# mini-v1_9.net
KiCad netlist of a schematic drawn in EAGLE
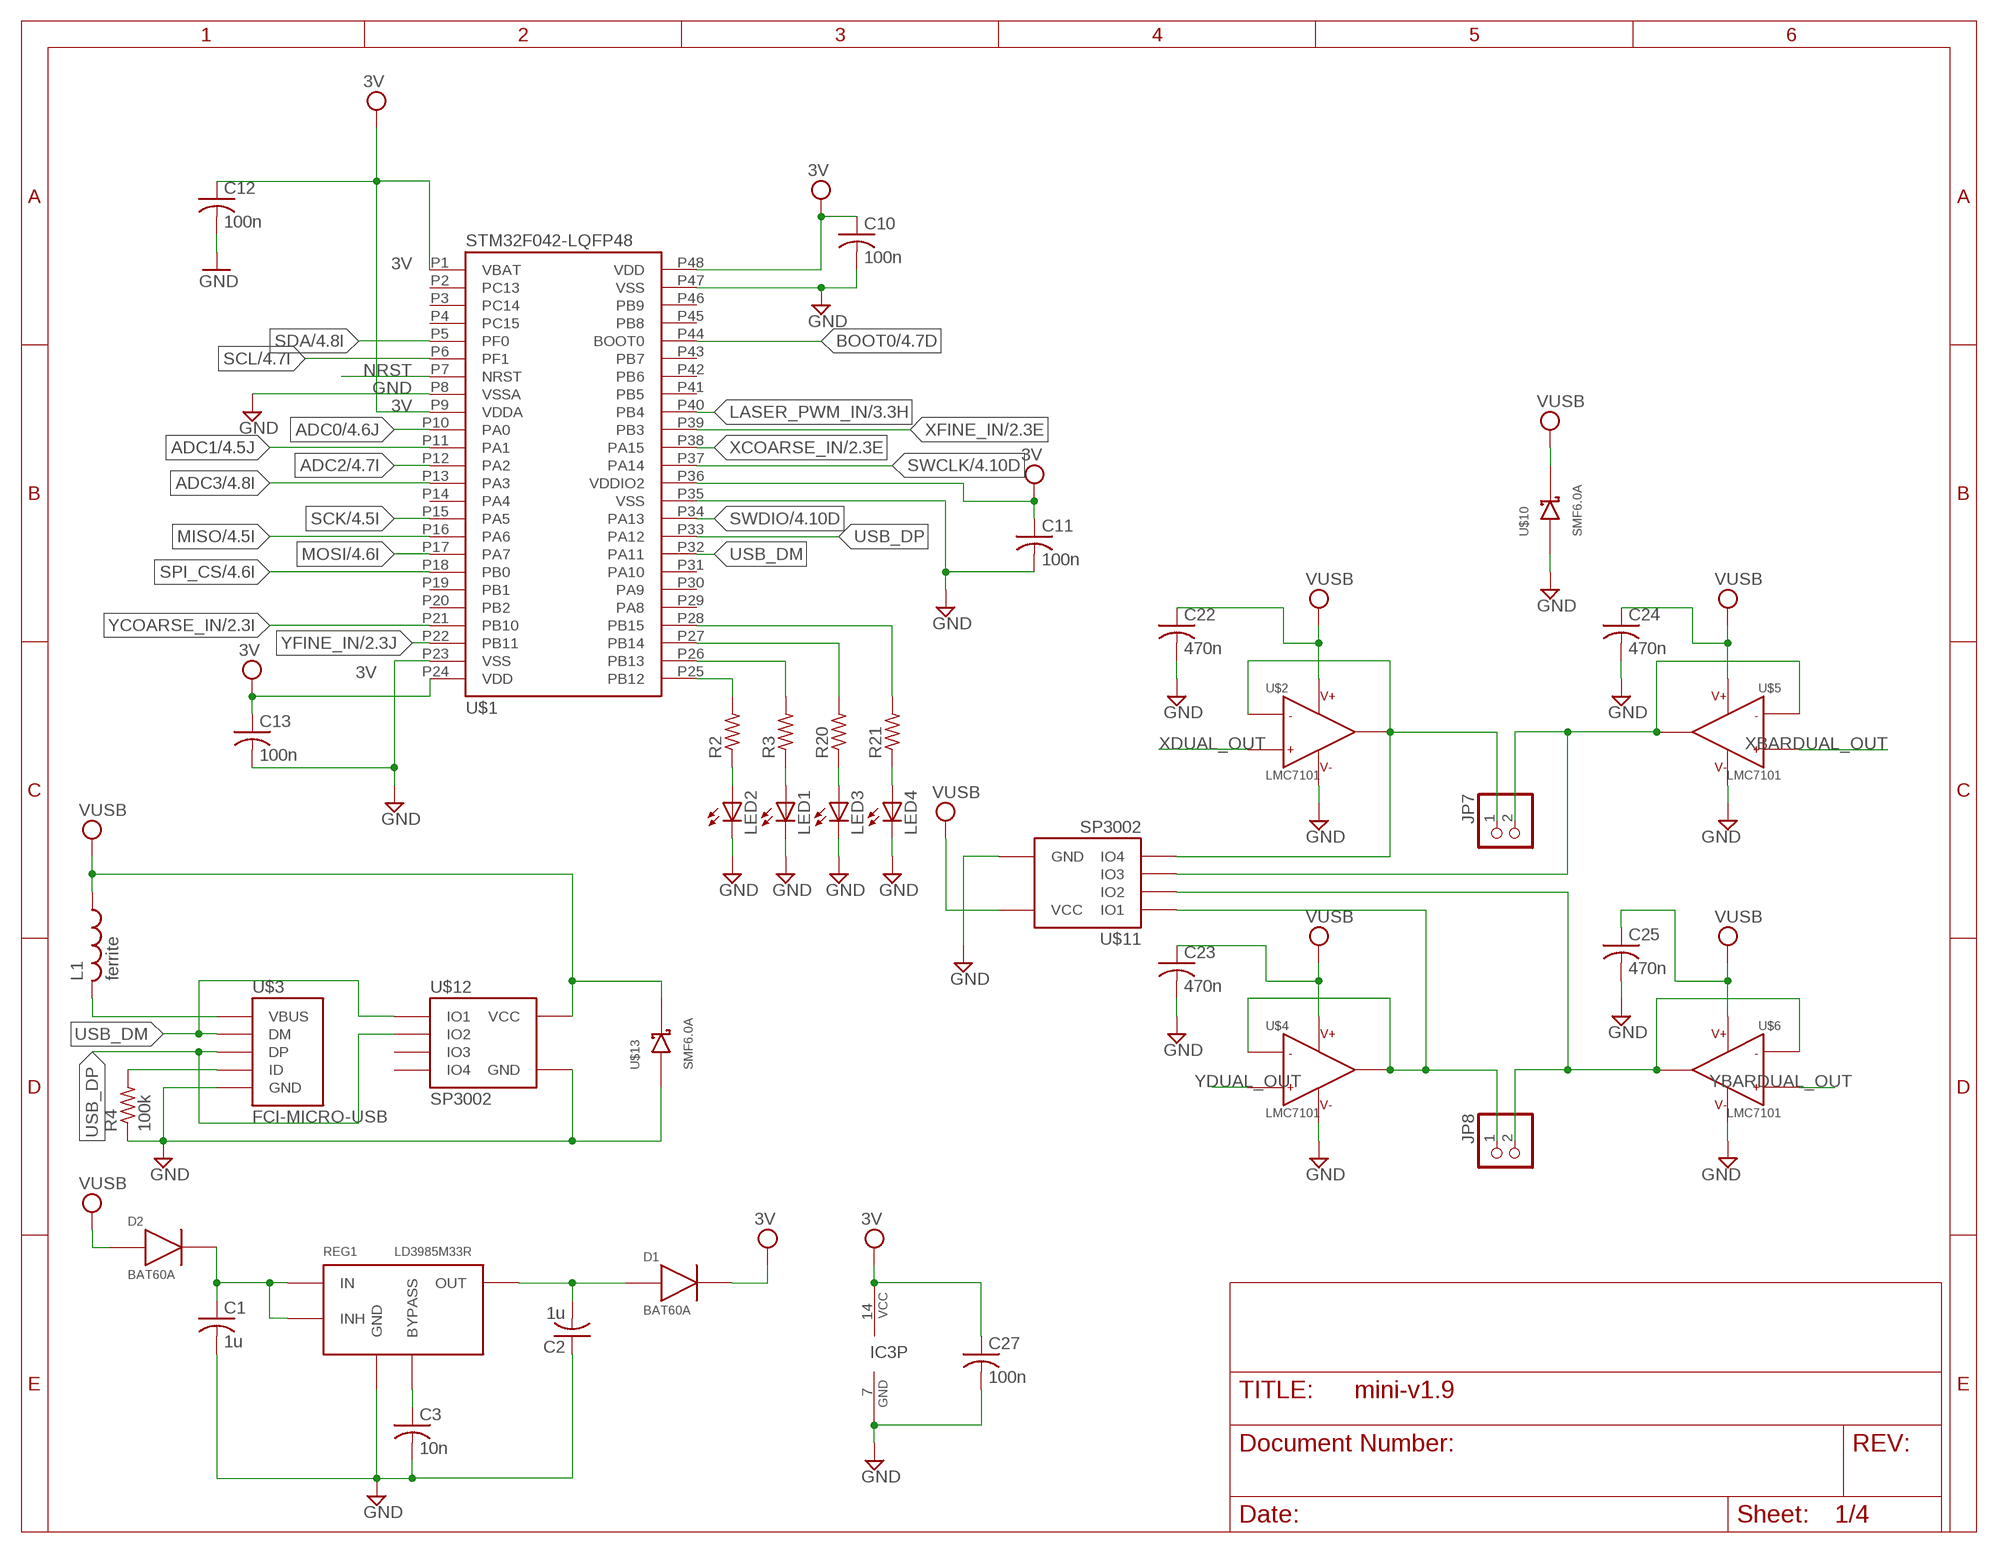
[diagram p0: schematic, sheet 1]
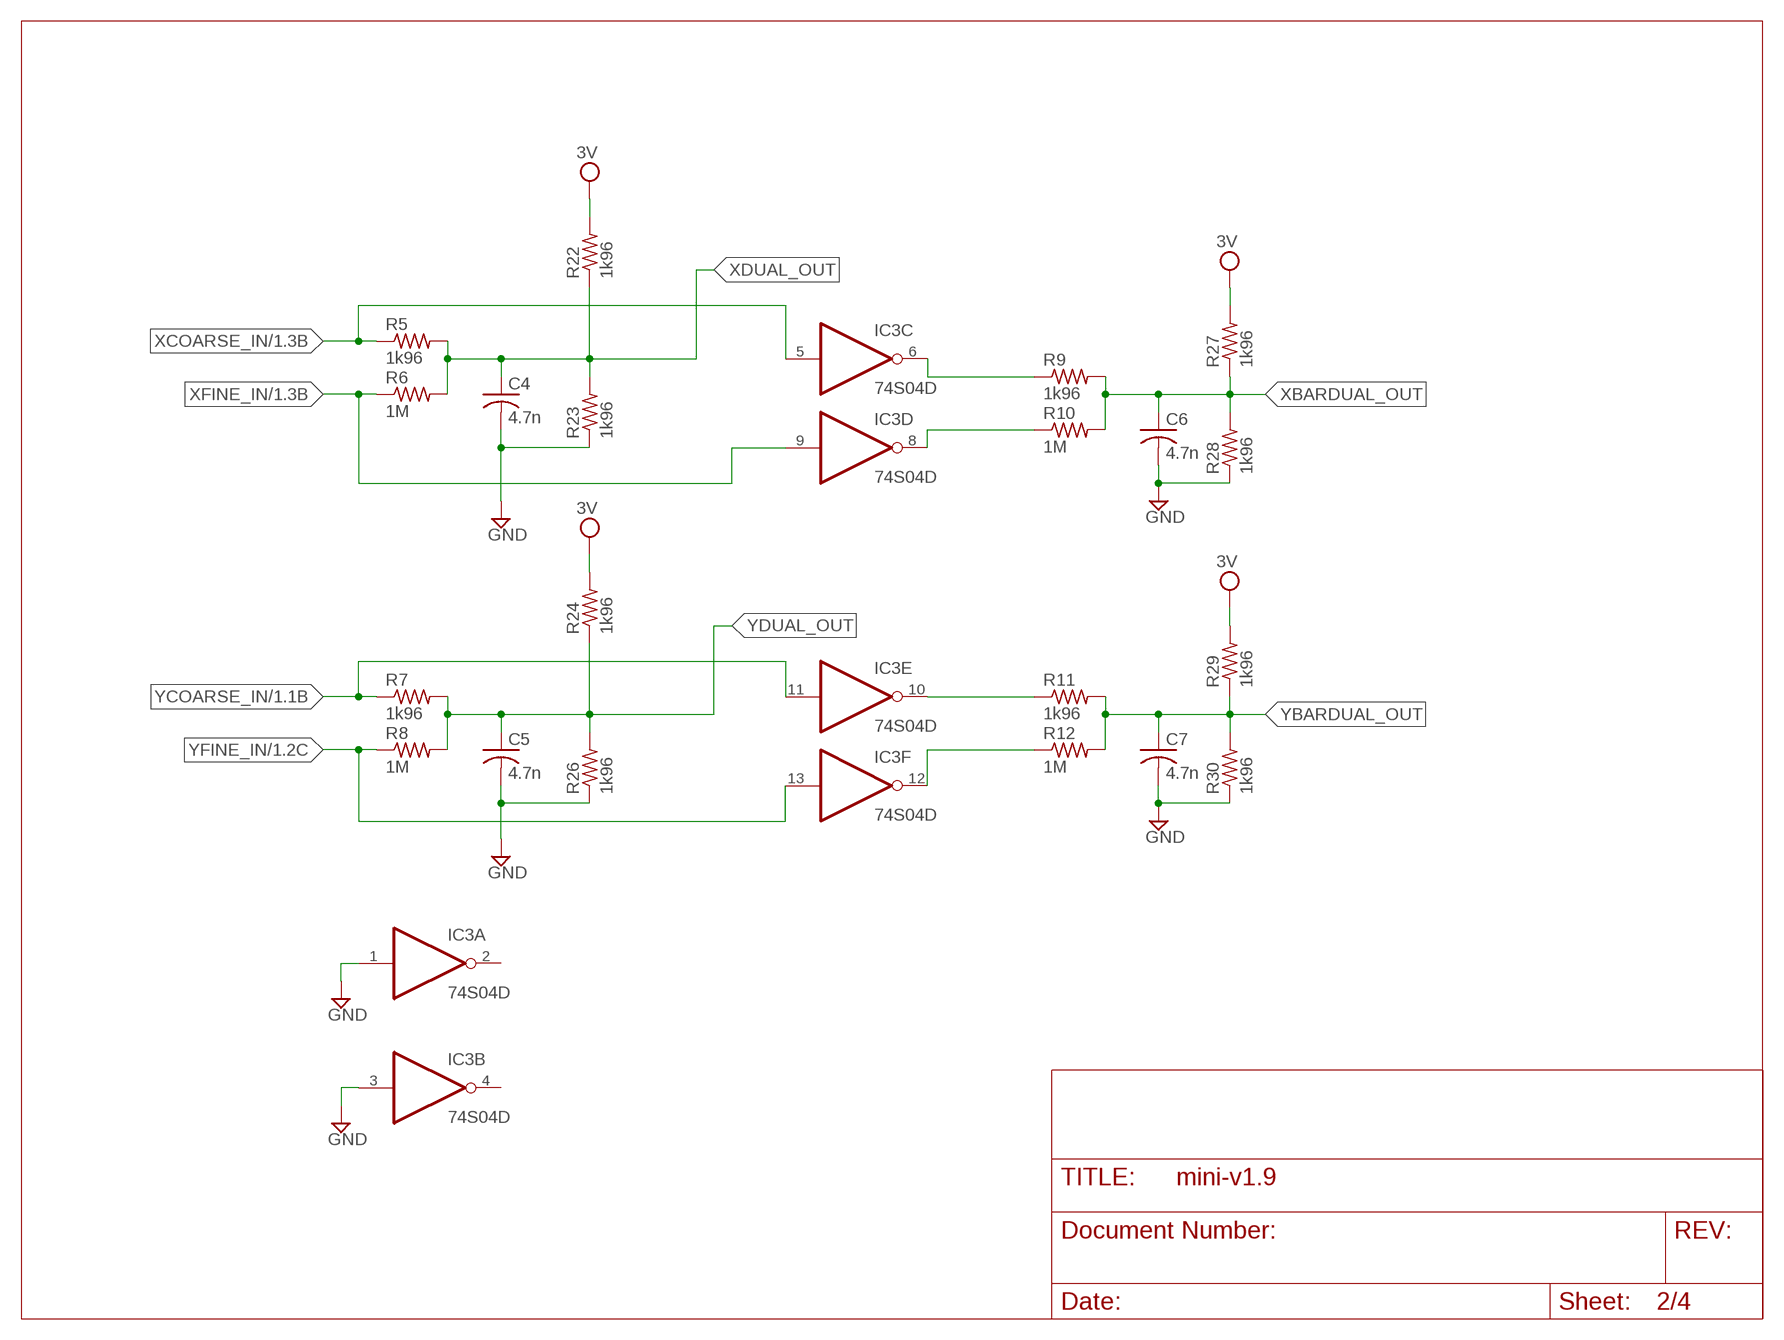
[diagram p1: schematic, sheet 2]
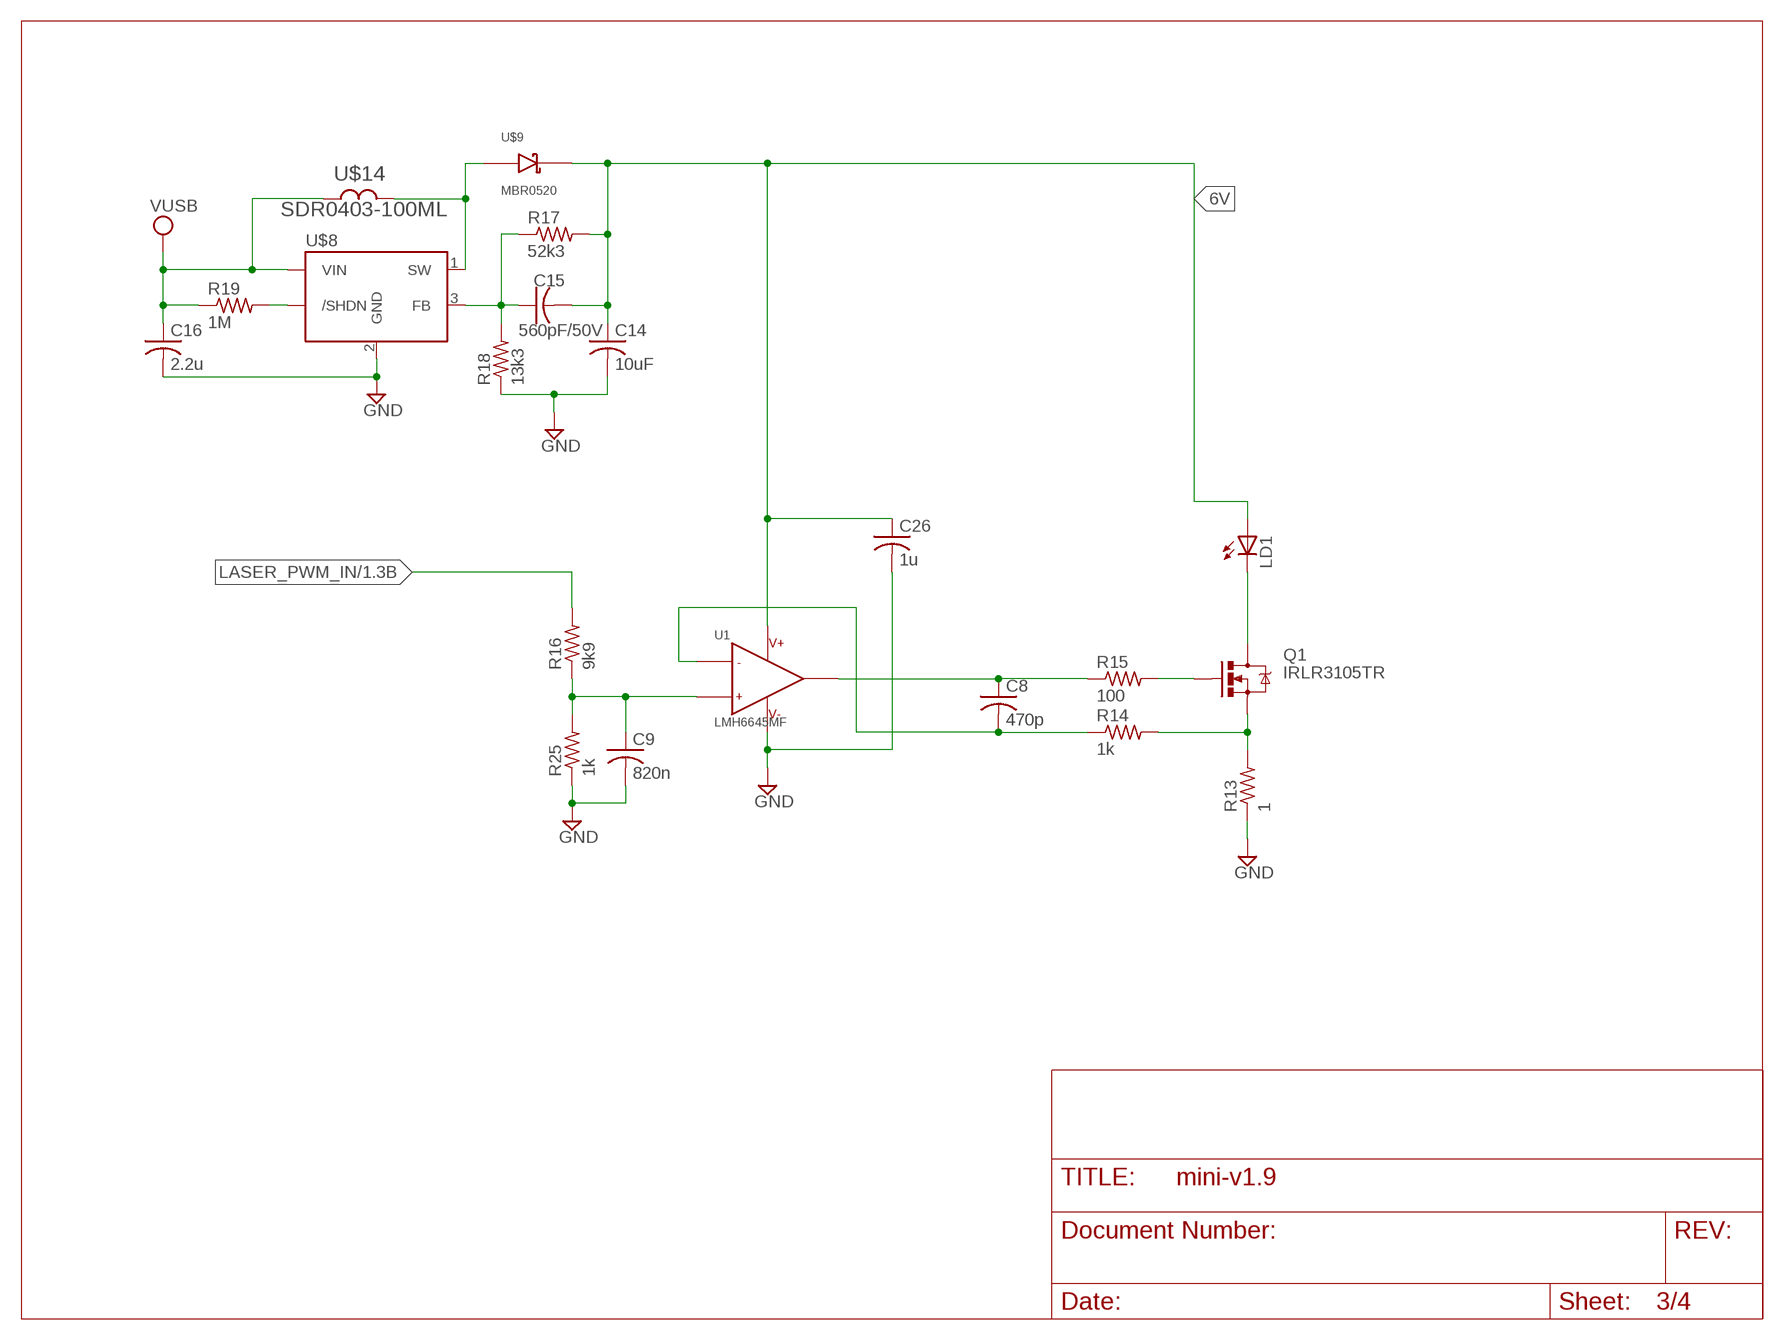
[diagram p2: schematic, sheet 3]
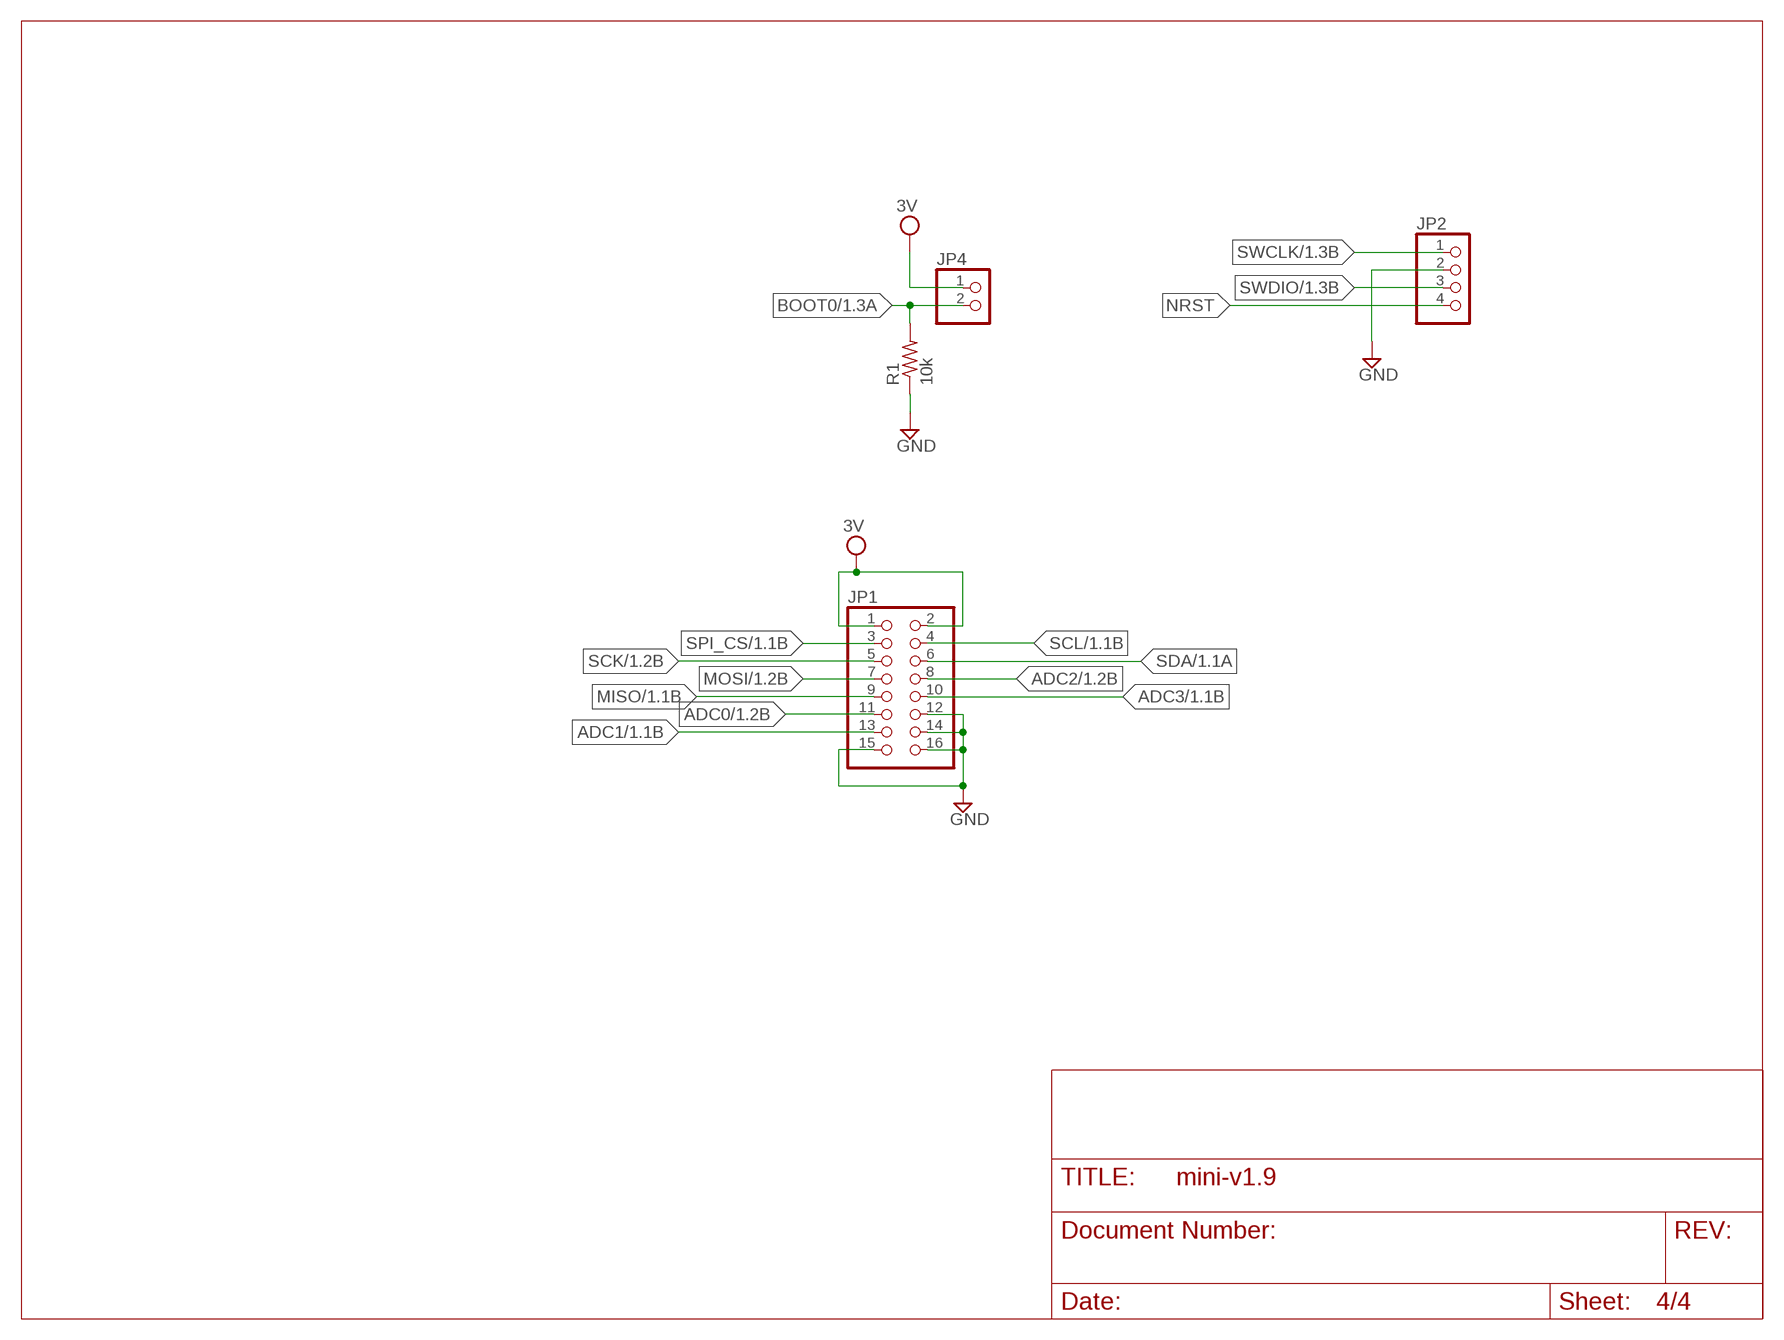
[diagram p3: schematic, sheet 4]

(export (version "E")
  (design (tool "Eeschema 10.0.6"))
  (components
    (comp (ref "JP1")
      (value "PINHD-2X8")
      (footprint "eagle-import:2X08")
      (libsource (lib "eagle-import") (part "PINHD-2X8"))
    )
    (comp (ref "JP2")
      (value "PINHD-1X4")
      (footprint "eagle-import:1X04")
      (libsource (lib "eagle-import") (part "PINHD-1X4"))
    )
    (comp (ref "JP4")
      (value "PINHD-1X2")
      (footprint "eagle-import:1X02")
      (libsource (lib "eagle-import") (part "PINHD-1X2"))
    )
    (comp (ref "R1")
      (value "10k")
      (footprint "eagle-import:R0603")
      (libsource (lib "eagle-import") (part "R-US_R0603"))
    )
    (comp (ref "C8")
      (value "470p")
      (footprint "eagle-import:C0603")
      (libsource (lib "eagle-import") (part "C-USC0603"))
    )
    (comp (ref "C9")
      (value "820n")
      (footprint "eagle-import:C0603")
      (libsource (lib "eagle-import") (part "C-USC0603"))
    )
    (comp (ref "C14")
      (value "10uF")
      (footprint "eagle-import:C0603")
      (libsource (lib "eagle-import") (part "C-USC0603"))
    )
    (comp (ref "C15")
      (value "560pF/50V")
      (footprint "eagle-import:C0603")
      (libsource (lib "eagle-import") (part "C-USC0603"))
    )
    (comp (ref "C16")
      (value "2.2u")
      (footprint "eagle-import:C0603")
      (libsource (lib "eagle-import") (part "C-USC0603"))
    )
    (comp (ref "C26")
      (value "1u")
      (footprint "eagle-import:C0603")
      (libsource (lib "eagle-import") (part "C-USC0603"))
    )
    (comp (ref "LD1")
      (value "LASERDIODELD2")
      (footprint "eagle-import:LASERDIODE2")
      (fields (field (name "MPN") "3 x (0552-2-15-15-11-27-10-0)"))
      (libsource (lib "eagle-import") (part "LASERDIODELD2"))
    )
    (comp (ref "Q1")
      (value "IRLR3105TR")
      (footprint "eagle-import:DPAK")
      (libsource (lib "eagle-import") (part "FET-N-IRLR3105TRIRLR3105TR"))
    )
    (comp (ref "R13")
      (value "1")
      (footprint "eagle-import:R0603")
      (libsource (lib "eagle-import") (part "R-US_R0603"))
    )
    (comp (ref "R14")
      (value "1k")
      (footprint "eagle-import:R0603")
      (libsource (lib "eagle-import") (part "R-US_R0603"))
    )
    (comp (ref "R15")
      (value "100")
      (footprint "eagle-import:R0603")
      (libsource (lib "eagle-import") (part "R-US_R0603"))
    )
    (comp (ref "R16")
      (value "9k9")
      (footprint "eagle-import:R0603")
      (libsource (lib "eagle-import") (part "R-US_R0603"))
    )
    (comp (ref "R17")
      (value "52k3")
      (footprint "eagle-import:R0603")
      (libsource (lib "eagle-import") (part "R-US_R0603"))
    )
    (comp (ref "R18")
      (value "13k3")
      (footprint "eagle-import:R0603")
      (libsource (lib "eagle-import") (part "R-US_R0603"))
    )
    (comp (ref "R19")
      (value "1M")
      (footprint "eagle-import:R0603")
      (libsource (lib "eagle-import") (part "R-US_R0603"))
    )
    (comp (ref "R25")
      (value "1k")
      (footprint "eagle-import:R0603")
      (libsource (lib "eagle-import") (part "R-US_R0603"))
    )
    (comp (ref "U$8")
      (value "LMR62014")
      (footprint "eagle-import:SOT23-5")
      (libsource (lib "eagle-import") (part "LMR62014"))
    )
    (comp (ref "U$9")
      (value "MBR0520")
      (footprint "eagle-import:SOD123")
      (libsource (lib "eagle-import") (part "MBR0520"))
    )
    (comp (ref "U$14")
      (value "SDR0403-100ML")
      (footprint "eagle-import:SDR0403")
      (libsource (lib "eagle-import") (part "SDR0403"))
    )
    (comp (ref "U1")
      (value "LMH6645MF")
      (footprint "eagle-import:SOT23-5")
      (libsource (lib "eagle-import") (part "OPAMP-SINGLELMH6645MF"))
    )
    (comp (ref "C1")
      (value "1u")
      (footprint "eagle-import:C0603")
      (libsource (lib "eagle-import") (part "C-USC0603"))
    )
    (comp (ref "C2")
      (value "1u")
      (footprint "eagle-import:C0603")
      (libsource (lib "eagle-import") (part "C-USC0603"))
    )
    (comp (ref "C3")
      (value "10n")
      (footprint "eagle-import:C0603")
      (libsource (lib "eagle-import") (part "C-USC0603"))
    )
    (comp (ref "C10")
      (value "100n")
      (footprint "eagle-import:C0603")
      (libsource (lib "eagle-import") (part "C-USC0603"))
    )
    (comp (ref "C11")
      (value "100n")
      (footprint "eagle-import:C0603")
      (libsource (lib "eagle-import") (part "C-USC0603"))
    )
    (comp (ref "C12")
      (value "100n")
      (footprint "eagle-import:C0603")
      (libsource (lib "eagle-import") (part "C-USC0603"))
    )
    (comp (ref "C13")
      (value "100n")
      (footprint "eagle-import:C0603")
      (libsource (lib "eagle-import") (part "C-USC0603"))
    )
    (comp (ref "C22")
      (value "470n")
      (footprint "eagle-import:C0603")
      (libsource (lib "eagle-import") (part "C-USC0603"))
    )
    (comp (ref "C23")
      (value "470n")
      (footprint "eagle-import:C0603")
      (libsource (lib "eagle-import") (part "C-USC0603"))
    )
    (comp (ref "C24")
      (value "470n")
      (footprint "eagle-import:C0603")
      (libsource (lib "eagle-import") (part "C-USC0603"))
    )
    (comp (ref "C25")
      (value "470n")
      (footprint "eagle-import:C0603")
      (libsource (lib "eagle-import") (part "C-USC0603"))
    )
    (comp (ref "C27")
      (value "100n")
      (footprint "eagle-import:C0603")
      (libsource (lib "eagle-import") (part "C-USC0603"))
    )
    (comp (ref "D1")
      (value "BAT60A")
      (footprint "eagle-import:SOD323")
      (libsource (lib "eagle-import") (part "BAT60A"))
    )
    (comp (ref "D2")
      (value "BAT60A")
      (footprint "eagle-import:SOD323")
      (libsource (lib "eagle-import") (part "BAT60A"))
    )
    (comp (ref "IC3")
      (value "74S04D")
      (footprint "eagle-import:SO14")
      (libsource (lib "eagle-import") (part "7404DS"))
    )
    (comp (ref "JP7")
      (value "PINHD-1X2")
      (footprint "eagle-import:1X02")
      (libsource (lib "eagle-import") (part "PINHD-1X2"))
    )
    (comp (ref "JP8")
      (value "PINHD-1X2")
      (footprint "eagle-import:1X02")
      (libsource (lib "eagle-import") (part "PINHD-1X2"))
    )
    (comp (ref "L1")
      (value "ferrite")
      (footprint "eagle-import:C0603")
      (libsource (lib "eagle-import") (part "L-US"))
    )
    (comp (ref "LED1")
      (value "LEDCHIP-LED0603")
      (footprint "eagle-import:CHIP-LED0603")
      (libsource (lib "eagle-import") (part "LEDCHIP-LED0603"))
    )
    (comp (ref "LED2")
      (value "LEDCHIP-LED0603")
      (footprint "eagle-import:CHIP-LED0603")
      (libsource (lib "eagle-import") (part "LEDCHIP-LED0603"))
    )
    (comp (ref "LED3")
      (value "LEDCHIP-LED0603")
      (footprint "eagle-import:CHIP-LED0603")
      (libsource (lib "eagle-import") (part "LEDCHIP-LED0603"))
    )
    (comp (ref "LED4")
      (value "LEDCHIP-LED0603")
      (footprint "eagle-import:CHIP-LED0603")
      (libsource (lib "eagle-import") (part "LEDCHIP-LED0603"))
    )
    (comp (ref "R2")
      (value "R-US_R0603")
      (footprint "eagle-import:R0603")
      (libsource (lib "eagle-import") (part "R-US_R0603"))
    )
    (comp (ref "R3")
      (value "R-US_R0603")
      (footprint "eagle-import:R0603")
      (libsource (lib "eagle-import") (part "R-US_R0603"))
    )
    (comp (ref "R4")
      (value "100k")
      (footprint "eagle-import:R0603")
      (libsource (lib "eagle-import") (part "R-US_R0603"))
    )
    (comp (ref "R20")
      (value "R-US_R0603")
      (footprint "eagle-import:R0603")
      (libsource (lib "eagle-import") (part "R-US_R0603"))
    )
    (comp (ref "R21")
      (value "R-US_R0603")
      (footprint "eagle-import:R0603")
      (libsource (lib "eagle-import") (part "R-US_R0603"))
    )
    (comp (ref "REG1")
      (value "LD3985M33R")
      (footprint "eagle-import:SOT23-5L")
      (libsource (lib "eagle-import") (part "LD3985MXXR"))
    )
    (comp (ref "U$1")
      (value "STM32F042-LQFP48")
      (footprint "eagle-import:LQFP48")
      (libsource (lib "eagle-import") (part "STM32F042-LQFP48"))
    )
    (comp (ref "U$2")
      (value "LMC7101")
      (footprint "eagle-import:SOT23-5")
      (libsource (lib "eagle-import") (part "LMC7101"))
    )
    (comp (ref "U$3")
      (value "FCI-MICRO-USB")
      (footprint "eagle-import:FCI-MICROUSB")
      (libsource (lib "eagle-import") (part "FCI-MICRO-USB"))
    )
    (comp (ref "U$4")
      (value "LMC7101")
      (footprint "eagle-import:SOT23-5")
      (libsource (lib "eagle-import") (part "LMC7101"))
    )
    (comp (ref "U$5")
      (value "LMC7101")
      (footprint "eagle-import:SOT23-5")
      (libsource (lib "eagle-import") (part "LMC7101"))
    )
    (comp (ref "U$6")
      (value "LMC7101")
      (footprint "eagle-import:SOT23-5")
      (libsource (lib "eagle-import") (part "LMC7101"))
    )
    (comp (ref "U$10")
      (value "SMF6.0A")
      (footprint "eagle-import:SOD123")
      (libsource (lib "eagle-import") (part "MBR0520"))
    )
    (comp (ref "U$11")
      (value "SP3002")
      (footprint "eagle-import:SC70-6")
      (libsource (lib "eagle-import") (part "SP3002"))
    )
    (comp (ref "U$12")
      (value "SP3002")
      (footprint "eagle-import:SC70-6")
      (libsource (lib "eagle-import") (part "SP3002"))
    )
    (comp (ref "U$13")
      (value "SMF6.0A")
      (footprint "eagle-import:SOD123")
      (libsource (lib "eagle-import") (part "MBR0520"))
    )
    (comp (ref "C4")
      (value "4.7n")
      (footprint "eagle-import:C0603")
      (libsource (lib "eagle-import") (part "C-USC0603"))
    )
    (comp (ref "C5")
      (value "4.7n")
      (footprint "eagle-import:C0603")
      (libsource (lib "eagle-import") (part "C-USC0603"))
    )
    (comp (ref "C6")
      (value "4.7n")
      (footprint "eagle-import:C0603")
      (libsource (lib "eagle-import") (part "C-USC0603"))
    )
    (comp (ref "C7")
      (value "4.7n")
      (footprint "eagle-import:C0603")
      (libsource (lib "eagle-import") (part "C-USC0603"))
    )
    (comp (ref "R5")
      (value "1k96")
      (footprint "eagle-import:R0603")
      (libsource (lib "eagle-import") (part "R-US_R0603"))
    )
    (comp (ref "R6")
      (value "1M")
      (footprint "eagle-import:R0603")
      (libsource (lib "eagle-import") (part "R-US_R0603"))
    )
    (comp (ref "R7")
      (value "1k96")
      (footprint "eagle-import:R0603")
      (libsource (lib "eagle-import") (part "R-US_R0603"))
    )
    (comp (ref "R8")
      (value "1M")
      (footprint "eagle-import:R0603")
      (libsource (lib "eagle-import") (part "R-US_R0603"))
    )
    (comp (ref "R9")
      (value "1k96")
      (footprint "eagle-import:R0603")
      (libsource (lib "eagle-import") (part "R-US_R0603"))
    )
    (comp (ref "R10")
      (value "1M")
      (footprint "eagle-import:R0603")
      (libsource (lib "eagle-import") (part "R-US_R0603"))
    )
    (comp (ref "R11")
      (value "1k96")
      (footprint "eagle-import:R0603")
      (libsource (lib "eagle-import") (part "R-US_R0603"))
    )
    (comp (ref "R12")
      (value "1M")
      (footprint "eagle-import:R0603")
      (libsource (lib "eagle-import") (part "R-US_R0603"))
    )
    (comp (ref "R22")
      (value "1k96")
      (footprint "eagle-import:R0603")
      (libsource (lib "eagle-import") (part "R-US_R0603"))
    )
    (comp (ref "R23")
      (value "1k96")
      (footprint "eagle-import:R0603")
      (libsource (lib "eagle-import") (part "R-US_R0603"))
    )
    (comp (ref "R24")
      (value "1k96")
      (footprint "eagle-import:R0603")
      (libsource (lib "eagle-import") (part "R-US_R0603"))
    )
    (comp (ref "R26")
      (value "1k96")
      (footprint "eagle-import:R0603")
      (libsource (lib "eagle-import") (part "R-US_R0603"))
    )
    (comp (ref "R27")
      (value "1k96")
      (footprint "eagle-import:R0603")
      (libsource (lib "eagle-import") (part "R-US_R0603"))
    )
    (comp (ref "R28")
      (value "1k96")
      (footprint "eagle-import:R0603")
      (libsource (lib "eagle-import") (part "R-US_R0603"))
    )
    (comp (ref "R29")
      (value "1k96")
      (footprint "eagle-import:R0603")
      (libsource (lib "eagle-import") (part "R-US_R0603"))
    )
    (comp (ref "R30")
      (value "1k96")
      (footprint "eagle-import:R0603")
      (libsource (lib "eagle-import") (part "R-US_R0603"))
    )
  )
  (nets
    (net (code "1") (name "3V") (class "Default")
      (node (ref "C10") (pin "1") (pinfunction "1_1") (pintype "passive"))
      (node (ref "C11") (pin "1") (pinfunction "1_1") (pintype "passive"))
      (node (ref "C12") (pin "1") (pinfunction "1_1") (pintype "passive"))
      (node (ref "C13") (pin "1") (pinfunction "1_1") (pintype "passive"))
      (node (ref "C27") (pin "1") (pinfunction "1_1") (pintype "passive"))
      (node (ref "D1") (pin "1") (pinfunction "1_1") (pintype "bidirectional"))
      (node (ref "IC3") (pin "14") (pinfunction "VCC_14") (pintype "power_in"))
      (node (ref "JP1") (pin "1") (pinfunction "1_1") (pintype "passive"))
      (node (ref "JP1") (pin "2") (pinfunction "2_2") (pintype "passive"))
      (node (ref "JP4") (pin "1") (pinfunction "1_1") (pintype "passive"))
      (node (ref "R22") (pin "2") (pinfunction "2_2") (pintype "passive"))
      (node (ref "R24") (pin "2") (pinfunction "2_2") (pintype "passive"))
      (node (ref "R27") (pin "2") (pinfunction "2_2") (pintype "passive"))
      (node (ref "R29") (pin "2") (pinfunction "2_2") (pintype "passive"))
      (node (ref "U$1") (pin "P1") (pinfunction "VBAT_P1") (pintype "bidirectional"))
      (node (ref "U$1") (pin "P24") (pinfunction "VDD_P24") (pintype "bidirectional"))
      (node (ref "U$1") (pin "P36") (pinfunction "VDDIO2_P36") (pintype "bidirectional"))
      (node (ref "U$1") (pin "P48") (pinfunction "VDD_P48") (pintype "bidirectional"))
      (node (ref "U$1") (pin "P9") (pinfunction "VDDA_P9") (pintype "bidirectional"))
    )
    (net (code "2") (name "6V") (class "Default")
      (node (ref "C14") (pin "1") (pinfunction "1_1") (pintype "passive"))
      (node (ref "C15") (pin "2") (pinfunction "2_2") (pintype "passive"))
      (node (ref "C26") (pin "1") (pinfunction "1_1") (pintype "passive"))
      (node (ref "LD1") (pin "P$1") (pinfunction "A_P$1") (pintype "passive"))
      (node (ref "R17") (pin "2") (pinfunction "2_2") (pintype "passive"))
      (node (ref "U$9") (pin "CATHODE") (pinfunction "CATHODE_CATHODE") (pintype "bidirectional"))
      (node (ref "U1") (pin "5") (pinfunction "V+_5") (pintype "power_in"))
    )
    (net (code "3") (name "ADC0") (class "Default")
      (node (ref "JP1") (pin "11") (pinfunction "11_11") (pintype "passive"))
      (node (ref "U$1") (pin "P10") (pinfunction "PA0_P10") (pintype "bidirectional"))
    )
    (net (code "4") (name "ADC1") (class "Default")
      (node (ref "JP1") (pin "13") (pinfunction "13_13") (pintype "passive"))
      (node (ref "U$1") (pin "P11") (pinfunction "PA1_P11") (pintype "bidirectional"))
    )
    (net (code "5") (name "ADC2") (class "Default")
      (node (ref "JP1") (pin "8") (pinfunction "8_8") (pintype "passive"))
      (node (ref "U$1") (pin "P12") (pinfunction "PA2_P12") (pintype "bidirectional"))
    )
    (net (code "6") (name "ADC3") (class "Default")
      (node (ref "JP1") (pin "10") (pinfunction "10_10") (pintype "passive"))
      (node (ref "U$1") (pin "P13") (pinfunction "PA3_P13") (pintype "bidirectional"))
    )
    (net (code "7") (name "BOOT0") (class "Default")
      (node (ref "JP4") (pin "2") (pinfunction "2_2") (pintype "passive"))
      (node (ref "R1") (pin "2") (pinfunction "2_2") (pintype "passive"))
      (node (ref "U$1") (pin "P44") (pinfunction "BOOT0_P44") (pintype "bidirectional"))
    )
    (net (code "8") (name "GND") (class "Default")
      (node (ref "C1") (pin "2") (pinfunction "2_2") (pintype "passive"))
      (node (ref "C10") (pin "2") (pinfunction "2_2") (pintype "passive"))
      (node (ref "C11") (pin "2") (pinfunction "2_2") (pintype "passive"))
      (node (ref "C12") (pin "2") (pinfunction "2_2") (pintype "passive"))
      (node (ref "C13") (pin "2") (pinfunction "2_2") (pintype "passive"))
      (node (ref "C14") (pin "2") (pinfunction "2_2") (pintype "passive"))
      (node (ref "C16") (pin "2") (pinfunction "2_2") (pintype "passive"))
      (node (ref "C2") (pin "1") (pinfunction "1_1") (pintype "passive"))
      (node (ref "C22") (pin "2") (pinfunction "2_2") (pintype "passive"))
      (node (ref "C23") (pin "2") (pinfunction "2_2") (pintype "passive"))
      (node (ref "C24") (pin "2") (pinfunction "2_2") (pintype "passive"))
      (node (ref "C25") (pin "2") (pinfunction "2_2") (pintype "passive"))
      (node (ref "C26") (pin "2") (pinfunction "2_2") (pintype "passive"))
      (node (ref "C27") (pin "2") (pinfunction "2_2") (pintype "passive"))
      (node (ref "C3") (pin "2") (pinfunction "2_2") (pintype "passive"))
      (node (ref "C4") (pin "2") (pinfunction "2_2") (pintype "passive"))
      (node (ref "C5") (pin "2") (pinfunction "2_2") (pintype "passive"))
      (node (ref "C6") (pin "2") (pinfunction "2_2") (pintype "passive"))
      (node (ref "C7") (pin "2") (pinfunction "2_2") (pintype "passive"))
      (node (ref "C9") (pin "2") (pinfunction "2_2") (pintype "passive"))
      (node (ref "IC3") (pin "1") (pinfunction "I_1") (pintype "input"))
      (node (ref "IC3") (pin "3") (pinfunction "I_3") (pintype "input"))
      (node (ref "IC3") (pin "7") (pinfunction "GND_7") (pintype "power_in"))
      (node (ref "JP1") (pin "12") (pinfunction "12_12") (pintype "passive"))
      (node (ref "JP1") (pin "14") (pinfunction "14_14") (pintype "passive"))
      (node (ref "JP1") (pin "15") (pinfunction "15_15") (pintype "passive"))
      (node (ref "JP1") (pin "16") (pinfunction "16_16") (pintype "passive"))
      (node (ref "JP2") (pin "2") (pinfunction "2_2") (pintype "passive"))
      (node (ref "LED1") (pin "C") (pinfunction "C_C") (pintype "passive"))
      (node (ref "LED2") (pin "C") (pinfunction "C_C") (pintype "passive"))
      (node (ref "LED3") (pin "C") (pinfunction "C_C") (pintype "passive"))
      (node (ref "LED4") (pin "C") (pinfunction "C_C") (pintype "passive"))
      (node (ref "R1") (pin "1") (pinfunction "1_1") (pintype "passive"))
      (node (ref "R13") (pin "1") (pinfunction "1_1") (pintype "passive"))
      (node (ref "R18") (pin "1") (pinfunction "1_1") (pintype "passive"))
      (node (ref "R23") (pin "1") (pinfunction "1_1") (pintype "passive"))
      (node (ref "R25") (pin "1") (pinfunction "1_1") (pintype "passive"))
      (node (ref "R26") (pin "1") (pinfunction "1_1") (pintype "passive"))
      (node (ref "R28") (pin "1") (pinfunction "1_1") (pintype "passive"))
      (node (ref "R30") (pin "1") (pinfunction "1_1") (pintype "passive"))
      (node (ref "R4") (pin "1") (pinfunction "1_1") (pintype "passive"))
      (node (ref "REG1") (pin "GND") (pinfunction "GND_GND") (pintype "bidirectional"))
      (node (ref "U$1") (pin "P23") (pinfunction "VSS_P23") (pintype "bidirectional"))
      (node (ref "U$1") (pin "P35") (pinfunction "VSS_P35") (pintype "bidirectional"))
      (node (ref "U$1") (pin "P47") (pinfunction "VSS_P47") (pintype "bidirectional"))
      (node (ref "U$1") (pin "P8") (pinfunction "VSSA_P8") (pintype "bidirectional"))
      (node (ref "U$10") (pin "ANODE") (pinfunction "ANODE_ANODE") (pintype "bidirectional"))
      (node (ref "U$11") (pin "P2") (pinfunction "GND_P2") (pintype "power_in"))
      (node (ref "U$12") (pin "P2") (pinfunction "GND_P2") (pintype "power_in"))
      (node (ref "U$13") (pin "ANODE") (pinfunction "ANODE_ANODE") (pintype "bidirectional"))
      (node (ref "U$2") (pin "5") (pinfunction "P5_5") (pintype "power_in"))
      (node (ref "U$3") (pin "P5") (pinfunction "GND_P5") (pintype "bidirectional"))
      (node (ref "U$4") (pin "5") (pinfunction "P5_5") (pintype "power_in"))
      (node (ref "U$5") (pin "5") (pinfunction "P5_5") (pintype "power_in"))
      (node (ref "U$6") (pin "5") (pinfunction "P5_5") (pintype "power_in"))
      (node (ref "U$8") (pin "2") (pinfunction "GND_2") (pintype "bidirectional"))
      (node (ref "U1") (pin "2") (pinfunction "V-_2") (pintype "power_in"))
    )
    (net (code "9") (name "LASER_PWM_IN") (class "Default")
      (node (ref "R16") (pin "2") (pinfunction "2_2") (pintype "passive"))
      (node (ref "U$1") (pin "P40") (pinfunction "PB4_P40") (pintype "bidirectional"))
    )
    (net (code "10") (name "MISO") (class "Default")
      (node (ref "JP1") (pin "9") (pinfunction "9_9") (pintype "passive"))
      (node (ref "U$1") (pin "P16") (pinfunction "PA6_P16") (pintype "bidirectional"))
    )
    (net (code "11") (name "MOSI") (class "Default")
      (node (ref "JP1") (pin "7") (pinfunction "7_7") (pintype "passive"))
      (node (ref "U$1") (pin "P17") (pinfunction "PA7_P17") (pintype "bidirectional"))
    )
    (net (code "12") (name "NRST") (class "Default")
      (node (ref "JP2") (pin "4") (pinfunction "4_4") (pintype "passive"))
      (node (ref "U$1") (pin "P7") (pinfunction "NRST_P7") (pintype "bidirectional"))
    )
    (net (code "13") (name "Net-(C2-Pad2)") (class "Default")
      (node (ref "C2") (pin "2") (pinfunction "2_2") (pintype "passive"))
      (node (ref "D1") (pin "2") (pinfunction "2_2") (pintype "bidirectional"))
      (node (ref "REG1") (pin "OUT") (pinfunction "OUT_OUT") (pintype "bidirectional"))
    )
    (net (code "14") (name "Net-(C3-Pad1)") (class "Default")
      (node (ref "C3") (pin "1") (pinfunction "1_1") (pintype "passive"))
      (node (ref "REG1") (pin "BYPASS") (pinfunction "BYPASS_BYPASS") (pintype "bidirectional"))
    )
    (net (code "15") (name "Net-(IC3C-O)") (class "Default")
      (node (ref "IC3") (pin "6") (pinfunction "O_6") (pintype "output"))
      (node (ref "R9") (pin "1") (pinfunction "1_1") (pintype "passive"))
    )
    (net (code "16") (name "Net-(IC3D-O)") (class "Default")
      (node (ref "IC3") (pin "8") (pinfunction "O_8") (pintype "output"))
      (node (ref "R10") (pin "1") (pinfunction "1_1") (pintype "passive"))
    )
    (net (code "17") (name "Net-(IC3E-O)") (class "Default")
      (node (ref "IC3") (pin "10") (pinfunction "O_10") (pintype "output"))
      (node (ref "R11") (pin "1") (pinfunction "1_1") (pintype "passive"))
    )
    (net (code "18") (name "Net-(IC3F-O)") (class "Default")
      (node (ref "IC3") (pin "12") (pinfunction "O_12") (pintype "output"))
      (node (ref "R12") (pin "1") (pinfunction "1_1") (pintype "passive"))
    )
    (net (code "19") (name "Net-(LD1-C)") (class "Default")
      (node (ref "LD1") (pin "P$3") (pinfunction "C_P$3") (pintype "passive"))
      (node (ref "Q1") (pin "4") (pinfunction "D_4") (pintype "passive"))
    )
    (net (code "20") (name "Net-(LED1-PadA)") (class "Default")
      (node (ref "LED1") (pin "A") (pinfunction "A_A") (pintype "passive"))
      (node (ref "R3") (pin "1") (pinfunction "1_1") (pintype "passive"))
    )
    (net (code "21") (name "Net-(LED2-PadA)") (class "Default")
      (node (ref "LED2") (pin "A") (pinfunction "A_A") (pintype "passive"))
      (node (ref "R2") (pin "1") (pinfunction "1_1") (pintype "passive"))
    )
    (net (code "22") (name "Net-(LED3-PadA)") (class "Default")
      (node (ref "LED3") (pin "A") (pinfunction "A_A") (pintype "passive"))
      (node (ref "R20") (pin "1") (pinfunction "1_1") (pintype "passive"))
    )
    (net (code "23") (name "Net-(LED4-PadA)") (class "Default")
      (node (ref "LED4") (pin "A") (pinfunction "A_A") (pintype "passive"))
      (node (ref "R21") (pin "1") (pinfunction "1_1") (pintype "passive"))
    )
    (net (code "24") (name "Net-(Q1-G)") (class "Default")
      (node (ref "Q1") (pin "1") (pinfunction "G_1") (pintype "passive"))
      (node (ref "R15") (pin "2") (pinfunction "2_2") (pintype "passive"))
    )
    (net (code "25") (name "Net-(Q1-S)") (class "Default")
      (node (ref "Q1") (pin "3") (pinfunction "S_3") (pintype "passive"))
      (node (ref "R13") (pin "2") (pinfunction "2_2") (pintype "passive"))
      (node (ref "R14") (pin "2") (pinfunction "2_2") (pintype "passive"))
    )
    (net (code "26") (name "Net-(REG1-INH)") (class "Default")
      (node (ref "C1") (pin "1") (pinfunction "1_1") (pintype "passive"))
      (node (ref "D2") (pin "1") (pinfunction "1_1") (pintype "bidirectional"))
      (node (ref "REG1") (pin "IN") (pinfunction "IN_IN") (pintype "bidirectional"))
      (node (ref "REG1") (pin "INHIBIT") (pinfunction "INH_INHIBIT") (pintype "bidirectional"))
    )
    (net (code "27") (name "Net-(U$1-PB12)") (class "Default")
      (node (ref "R2") (pin "2") (pinfunction "2_2") (pintype "passive"))
      (node (ref "U$1") (pin "P25") (pinfunction "PB12_P25") (pintype "bidirectional"))
    )
    (net (code "28") (name "Net-(U$1-PB13)") (class "Default")
      (node (ref "R3") (pin "2") (pinfunction "2_2") (pintype "passive"))
      (node (ref "U$1") (pin "P26") (pinfunction "PB13_P26") (pintype "bidirectional"))
    )
    (net (code "29") (name "Net-(U$1-PB14)") (class "Default")
      (node (ref "R20") (pin "2") (pinfunction "2_2") (pintype "passive"))
      (node (ref "U$1") (pin "P27") (pinfunction "PB14_P27") (pintype "bidirectional"))
    )
    (net (code "30") (name "Net-(U$1-PB15)") (class "Default")
      (node (ref "R21") (pin "2") (pinfunction "2_2") (pintype "passive"))
      (node (ref "U$1") (pin "P28") (pinfunction "PB15_P28") (pintype "bidirectional"))
    )
    (net (code "31") (name "Net-(U$3-ID)") (class "Default")
      (node (ref "R4") (pin "2") (pinfunction "2_2") (pintype "passive"))
      (node (ref "U$3") (pin "P4") (pinfunction "ID_P4") (pintype "bidirectional"))
    )
    (net (code "32") (name "Net-(U$3-VBUS)") (class "Default")
      (node (ref "L1") (pin "2") (pinfunction "2_2") (pintype "passive"))
      (node (ref "U$3") (pin "P1") (pinfunction "VBUS_P1") (pintype "bidirectional"))
    )
    (net (code "33") (name "Net-(U$8-FB)") (class "Default")
      (node (ref "C15") (pin "1") (pinfunction "1_1") (pintype "passive"))
      (node (ref "R17") (pin "1") (pinfunction "1_1") (pintype "passive"))
      (node (ref "R18") (pin "2") (pinfunction "2_2") (pintype "passive"))
      (node (ref "U$8") (pin "3") (pinfunction "FB_3") (pintype "bidirectional"))
    )
    (net (code "34") (name "Net-(U$8-SW)") (class "Default")
      (node (ref "U$14") (pin "P$2") (pinfunction "P$2_P$2") (pintype "bidirectional"))
      (node (ref "U$8") (pin "1") (pinfunction "SW_1") (pintype "bidirectional"))
      (node (ref "U$9") (pin "ANODE") (pinfunction "ANODE_ANODE") (pintype "bidirectional"))
    )
    (net (code "35") (name "Net-(U$8-{slash}SHDN)") (class "Default")
      (node (ref "R19") (pin "2") (pinfunction "2_2") (pintype "passive"))
      (node (ref "U$8") (pin "4") (pinfunction "/SHDN_4") (pintype "bidirectional"))
    )
    (net (code "36") (name "Net-(U$11-IO1)") (class "Default")
      (node (ref "JP8") (pin "1") (pinfunction "1_1") (pintype "passive"))
      (node (ref "U$11") (pin "P1") (pinfunction "IO1_P1") (pintype "bidirectional"))
      (node (ref "U$4") (pin "1") (pinfunction "P1_1") (pintype "bidirectional"))
      (node (ref "U$4") (pin "4") (pinfunction "P4_4") (pintype "bidirectional"))
    )
    (net (code "37") (name "Net-(U$11-IO2)") (class "Default")
      (node (ref "JP8") (pin "2") (pinfunction "2_2") (pintype "passive"))
      (node (ref "U$11") (pin "P3") (pinfunction "IO2_P3") (pintype "bidirectional"))
      (node (ref "U$6") (pin "1") (pinfunction "P1_1") (pintype "bidirectional"))
      (node (ref "U$6") (pin "4") (pinfunction "P4_4") (pintype "bidirectional"))
    )
    (net (code "38") (name "Net-(U$11-IO3)") (class "Default")
      (node (ref "JP7") (pin "2") (pinfunction "2_2") (pintype "passive"))
      (node (ref "U$11") (pin "P4") (pinfunction "IO3_P4") (pintype "bidirectional"))
      (node (ref "U$5") (pin "1") (pinfunction "P1_1") (pintype "bidirectional"))
      (node (ref "U$5") (pin "4") (pinfunction "P4_4") (pintype "bidirectional"))
    )
    (net (code "39") (name "Net-(U$11-IO4)") (class "Default")
      (node (ref "JP7") (pin "1") (pinfunction "1_1") (pintype "passive"))
      (node (ref "U$11") (pin "P6") (pinfunction "IO4_P6") (pintype "bidirectional"))
      (node (ref "U$2") (pin "1") (pinfunction "P1_1") (pintype "bidirectional"))
      (node (ref "U$2") (pin "4") (pinfunction "P4_4") (pintype "bidirectional"))
    )
    (net (code "40") (name "Net-(U1-IN+)") (class "Default")
      (node (ref "C9") (pin "1") (pinfunction "1_1") (pintype "passive"))
      (node (ref "R16") (pin "1") (pinfunction "1_1") (pintype "passive"))
      (node (ref "R25") (pin "2") (pinfunction "2_2") (pintype "passive"))
      (node (ref "U1") (pin "3") (pinfunction "IN+_3") (pintype "bidirectional"))
    )
    (net (code "41") (name "Net-(U1-IN-)") (class "Default")
      (node (ref "C8") (pin "2") (pinfunction "2_2") (pintype "passive"))
      (node (ref "R14") (pin "1") (pinfunction "1_1") (pintype "passive"))
      (node (ref "U1") (pin "4") (pinfunction "IN-_4") (pintype "bidirectional"))
    )
    (net (code "42") (name "Net-(U1-OUT)") (class "Default")
      (node (ref "C8") (pin "1") (pinfunction "1_1") (pintype "passive"))
      (node (ref "R15") (pin "1") (pinfunction "1_1") (pintype "passive"))
      (node (ref "U1") (pin "1") (pinfunction "OUT_1") (pintype "bidirectional"))
    )
    (net (code "43") (name "SCK") (class "Default")
      (node (ref "JP1") (pin "5") (pinfunction "5_5") (pintype "passive"))
      (node (ref "U$1") (pin "P15") (pinfunction "PA5_P15") (pintype "bidirectional"))
    )
    (net (code "44") (name "SCL") (class "Default")
      (node (ref "JP1") (pin "4") (pinfunction "4_4") (pintype "passive"))
      (node (ref "U$1") (pin "P6") (pinfunction "PF1_P6") (pintype "bidirectional"))
    )
    (net (code "45") (name "SDA") (class "Default")
      (node (ref "JP1") (pin "6") (pinfunction "6_6") (pintype "passive"))
      (node (ref "U$1") (pin "P5") (pinfunction "PF0_P5") (pintype "bidirectional"))
    )
    (net (code "46") (name "SPI_CS") (class "Default")
      (node (ref "JP1") (pin "3") (pinfunction "3_3") (pintype "passive"))
      (node (ref "U$1") (pin "P18") (pinfunction "PB0_P18") (pintype "bidirectional"))
    )
    (net (code "47") (name "SWCLK") (class "Default")
      (node (ref "JP2") (pin "1") (pinfunction "1_1") (pintype "passive"))
      (node (ref "U$1") (pin "P37") (pinfunction "PA14_P37") (pintype "bidirectional"))
    )
    (net (code "48") (name "SWDIO") (class "Default")
      (node (ref "JP2") (pin "3") (pinfunction "3_3") (pintype "passive"))
      (node (ref "U$1") (pin "P34") (pinfunction "PA13_P34") (pintype "bidirectional"))
    )
    (net (code "49") (name "USB_DM") (class "Default")
      (node (ref "U$1") (pin "P32") (pinfunction "PA11_P32") (pintype "bidirectional"))
      (node (ref "U$12") (pin "P1") (pinfunction "IO1_P1") (pintype "bidirectional"))
      (node (ref "U$3") (pin "P2") (pinfunction "DM_P2") (pintype "bidirectional"))
    )
    (net (code "50") (name "USB_DP") (class "Default")
      (node (ref "U$1") (pin "P33") (pinfunction "PA12_P33") (pintype "bidirectional"))
      (node (ref "U$12") (pin "P3") (pinfunction "IO2_P3") (pintype "bidirectional"))
      (node (ref "U$3") (pin "P3") (pinfunction "DP_P3") (pintype "bidirectional"))
    )
    (net (code "51") (name "VUSB") (class "Default")
      (node (ref "C16") (pin "1") (pinfunction "1_1") (pintype "passive"))
      (node (ref "C22") (pin "1") (pinfunction "1_1") (pintype "passive"))
      (node (ref "C23") (pin "1") (pinfunction "1_1") (pintype "passive"))
      (node (ref "C24") (pin "1") (pinfunction "1_1") (pintype "passive"))
      (node (ref "C25") (pin "1") (pinfunction "1_1") (pintype "passive"))
      (node (ref "D2") (pin "2") (pinfunction "2_2") (pintype "bidirectional"))
      (node (ref "L1") (pin "1") (pinfunction "1_1") (pintype "passive"))
      (node (ref "R19") (pin "1") (pinfunction "1_1") (pintype "passive"))
      (node (ref "U$10") (pin "CATHODE") (pinfunction "CATHODE_CATHODE") (pintype "bidirectional"))
      (node (ref "U$11") (pin "P5") (pinfunction "VCC_P5") (pintype "power_in"))
      (node (ref "U$12") (pin "P5") (pinfunction "VCC_P5") (pintype "power_in"))
      (node (ref "U$13") (pin "CATHODE") (pinfunction "CATHODE_CATHODE") (pintype "bidirectional"))
      (node (ref "U$14") (pin "P$1") (pinfunction "P$1_P$1") (pintype "bidirectional"))
      (node (ref "U$2") (pin "2") (pinfunction "P2_2") (pintype "power_in"))
      (node (ref "U$4") (pin "2") (pinfunction "P2_2") (pintype "power_in"))
      (node (ref "U$5") (pin "2") (pinfunction "P2_2") (pintype "power_in"))
      (node (ref "U$6") (pin "2") (pinfunction "P2_2") (pintype "power_in"))
      (node (ref "U$8") (pin "5") (pinfunction "VIN_5") (pintype "bidirectional"))
    )
    (net (code "52") (name "XBARDUAL_OUT") (class "Default")
      (node (ref "C6") (pin "1") (pinfunction "1_1") (pintype "passive"))
      (node (ref "R10") (pin "2") (pinfunction "2_2") (pintype "passive"))
      (node (ref "R27") (pin "1") (pinfunction "1_1") (pintype "passive"))
      (node (ref "R28") (pin "2") (pinfunction "2_2") (pintype "passive"))
      (node (ref "R9") (pin "2") (pinfunction "2_2") (pintype "passive"))
      (node (ref "U$5") (pin "3") (pinfunction "P3_3") (pintype "bidirectional"))
    )
    (net (code "53") (name "XCOARSE_IN") (class "Default")
      (node (ref "IC3") (pin "5") (pinfunction "I_5") (pintype "input"))
      (node (ref "R5") (pin "1") (pinfunction "1_1") (pintype "passive"))
      (node (ref "U$1") (pin "P38") (pinfunction "PA15_P38") (pintype "bidirectional"))
    )
    (net (code "54") (name "XDUAL_OUT") (class "Default")
      (node (ref "C4") (pin "1") (pinfunction "1_1") (pintype "passive"))
      (node (ref "R22") (pin "1") (pinfunction "1_1") (pintype "passive"))
      (node (ref "R23") (pin "2") (pinfunction "2_2") (pintype "passive"))
      (node (ref "R5") (pin "2") (pinfunction "2_2") (pintype "passive"))
      (node (ref "R6") (pin "2") (pinfunction "2_2") (pintype "passive"))
      (node (ref "U$2") (pin "3") (pinfunction "P3_3") (pintype "bidirectional"))
    )
    (net (code "55") (name "XFINE_IN") (class "Default")
      (node (ref "IC3") (pin "9") (pinfunction "I_9") (pintype "input"))
      (node (ref "R6") (pin "1") (pinfunction "1_1") (pintype "passive"))
      (node (ref "U$1") (pin "P39") (pinfunction "PB3_P39") (pintype "bidirectional"))
    )
    (net (code "56") (name "YBARDUAL_OUT") (class "Default")
      (node (ref "C7") (pin "1") (pinfunction "1_1") (pintype "passive"))
      (node (ref "R11") (pin "2") (pinfunction "2_2") (pintype "passive"))
      (node (ref "R12") (pin "2") (pinfunction "2_2") (pintype "passive"))
      (node (ref "R29") (pin "1") (pinfunction "1_1") (pintype "passive"))
      (node (ref "R30") (pin "2") (pinfunction "2_2") (pintype "passive"))
      (node (ref "U$6") (pin "3") (pinfunction "P3_3") (pintype "bidirectional"))
    )
    (net (code "57") (name "YCOARSE_IN") (class "Default")
      (node (ref "IC3") (pin "11") (pinfunction "I_11") (pintype "input"))
      (node (ref "R7") (pin "1") (pinfunction "1_1") (pintype "passive"))
      (node (ref "U$1") (pin "P21") (pinfunction "PB10_P21") (pintype "bidirectional"))
    )
    (net (code "58") (name "YDUAL_OUT") (class "Default")
      (node (ref "C5") (pin "1") (pinfunction "1_1") (pintype "passive"))
      (node (ref "R24") (pin "1") (pinfunction "1_1") (pintype "passive"))
      (node (ref "R26") (pin "2") (pinfunction "2_2") (pintype "passive"))
      (node (ref "R7") (pin "2") (pinfunction "2_2") (pintype "passive"))
      (node (ref "R8") (pin "2") (pinfunction "2_2") (pintype "passive"))
      (node (ref "U$4") (pin "3") (pinfunction "P3_3") (pintype "bidirectional"))
    )
    (net (code "59") (name "YFINE_IN") (class "Default")
      (node (ref "IC3") (pin "13") (pinfunction "I_13") (pintype "input"))
      (node (ref "R8") (pin "1") (pinfunction "1_1") (pintype "passive"))
      (node (ref "U$1") (pin "P22") (pinfunction "PB11_P22") (pintype "bidirectional"))
    )
    (net (code "60") (name "unconnected-(IC3A-O-Pad2)") (class "Default")
      (node (ref "IC3") (pin "2") (pinfunction "O_2") (pintype "output"))
    )
    (net (code "61") (name "unconnected-(IC3B-O-Pad4)") (class "Default")
      (node (ref "IC3") (pin "4") (pinfunction "O_4") (pintype "output"))
    )
    (net (code "62") (name "unconnected-(U$1-PA4-PadP14)") (class "Default")
      (node (ref "U$1") (pin "P14") (pinfunction "PA4_P14") (pintype "bidirectional"))
    )
    (net (code "63") (name "unconnected-(U$1-PA8-PadP29)") (class "Default")
      (node (ref "U$1") (pin "P29") (pinfunction "PA8_P29") (pintype "bidirectional"))
    )
    (net (code "64") (name "unconnected-(U$1-PA9-PadP30)") (class "Default")
      (node (ref "U$1") (pin "P30") (pinfunction "PA9_P30") (pintype "bidirectional"))
    )
    (net (code "65") (name "unconnected-(U$1-PA10-PadP31)") (class "Default")
      (node (ref "U$1") (pin "P31") (pinfunction "PA10_P31") (pintype "bidirectional"))
    )
    (net (code "66") (name "unconnected-(U$1-PB1-PadP19)") (class "Default")
      (node (ref "U$1") (pin "P19") (pinfunction "PB1_P19") (pintype "bidirectional"))
    )
    (net (code "67") (name "unconnected-(U$1-PB2-PadP20)") (class "Default")
      (node (ref "U$1") (pin "P20") (pinfunction "PB2_P20") (pintype "bidirectional"))
    )
    (net (code "68") (name "unconnected-(U$1-PB5-PadP41)") (class "Default")
      (node (ref "U$1") (pin "P41") (pinfunction "PB5_P41") (pintype "bidirectional"))
    )
    (net (code "69") (name "unconnected-(U$1-PB6-PadP42)") (class "Default")
      (node (ref "U$1") (pin "P42") (pinfunction "PB6_P42") (pintype "bidirectional"))
    )
    (net (code "70") (name "unconnected-(U$1-PB7-PadP43)") (class "Default")
      (node (ref "U$1") (pin "P43") (pinfunction "PB7_P43") (pintype "bidirectional"))
    )
    (net (code "71") (name "unconnected-(U$1-PB8-PadP45)") (class "Default")
      (node (ref "U$1") (pin "P45") (pinfunction "PB8_P45") (pintype "bidirectional"))
    )
    (net (code "72") (name "unconnected-(U$1-PB9-PadP46)") (class "Default")
      (node (ref "U$1") (pin "P46") (pinfunction "PB9_P46") (pintype "bidirectional"))
    )
    (net (code "73") (name "unconnected-(U$1-PC13-PadP2)") (class "Default")
      (node (ref "U$1") (pin "P2") (pinfunction "PC13_P2") (pintype "bidirectional"))
    )
    (net (code "74") (name "unconnected-(U$1-PC14-PadP3)") (class "Default")
      (node (ref "U$1") (pin "P3") (pinfunction "PC14_P3") (pintype "bidirectional"))
    )
    (net (code "75") (name "unconnected-(U$1-PC15-PadP4)") (class "Default")
      (node (ref "U$1") (pin "P4") (pinfunction "PC15_P4") (pintype "bidirectional"))
    )
    (net (code "76") (name "unconnected-(U$12-IO3-PadP4)") (class "Default")
      (node (ref "U$12") (pin "P4") (pinfunction "IO3_P4") (pintype "bidirectional"))
    )
    (net (code "77") (name "unconnected-(U$12-IO4-PadP6)") (class "Default")
      (node (ref "U$12") (pin "P6") (pinfunction "IO4_P6") (pintype "bidirectional"))
    )
  )
)
